# 10_LMS3_RF.net
KiCad netlist of a schematic drawn in Altium Designer
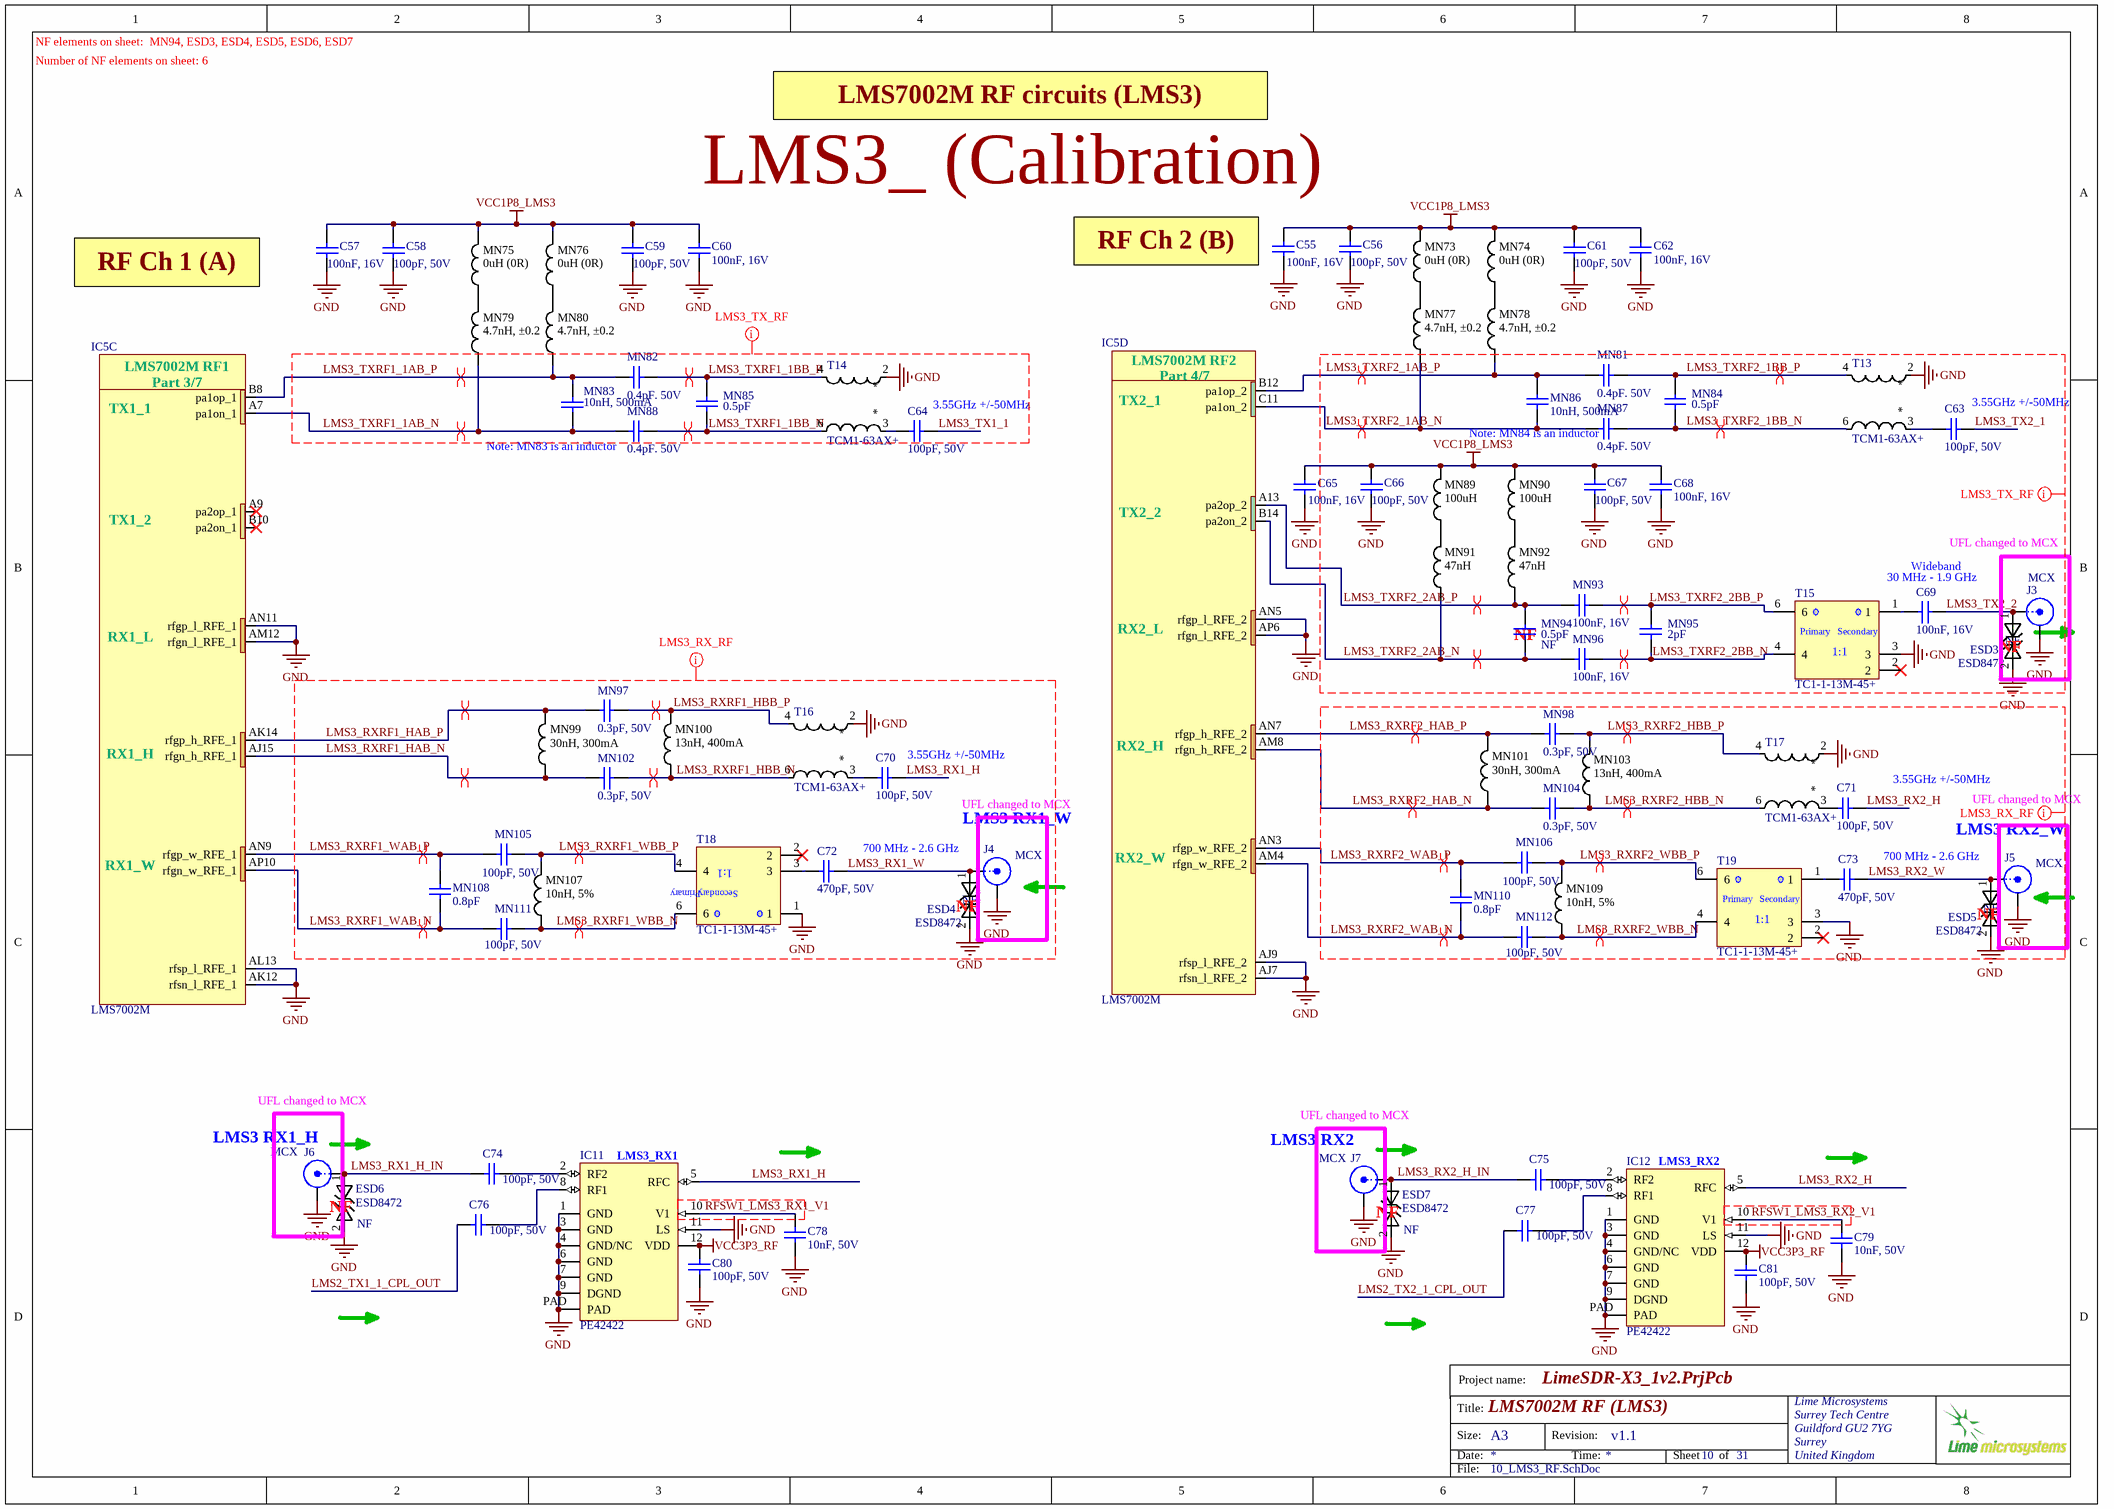
[diagram p0: 10_LMS3_RF.SchDoc]

(export (version "E")
  (design (tool "Eeschema 10.0.6"))
  (components
    (comp (ref "C55")
      (value "100nF, 16V")
      (footprint "CAP0402")
      (fields (field (name "MANUFACTURER") "Murata Electronics") (field (name "TOLERANCE") "10 %"))
      (libsource (lib "") (part "Cap_0402_5"))
    )
    (comp (ref "C56")
      (value "100pF, 50V")
      (footprint "CAP0402")
      (fields (field (name "MANUFACTURER") "Yageo") (field (name "TOLERANCE") "±5%"))
      (libsource (lib "") (part "Cap_0402_2"))
    )
    (comp (ref "C57")
      (value "100nF, 16V")
      (footprint "CAP0402")
      (fields (field (name "MANUFACTURER") "Murata Electronics") (field (name "TOLERANCE") "10 %"))
      (libsource (lib "") (part "Cap_0402_7"))
    )
    (comp (ref "C58")
      (value "100pF, 50V")
      (footprint "CAP0402")
      (fields (field (name "MANUFACTURER") "Yageo") (field (name "TOLERANCE") "±5%"))
      (libsource (lib "") (part "Cap_0402_2"))
    )
    (comp (ref "C59")
      (value "100pF, 50V")
      (footprint "CAP0402")
      (fields (field (name "MANUFACTURER") "Yageo") (field (name "TOLERANCE") "±5%"))
      (libsource (lib "") (part "Cap_0402_2"))
    )
    (comp (ref "C60")
      (value "100nF, 16V")
      (footprint "CAP0402")
      (fields (field (name "MANUFACTURER") "Murata Electronics") (field (name "TOLERANCE") "10 %"))
      (libsource (lib "") (part "Cap_0402_7"))
    )
    (comp (ref "C61")
      (value "100pF, 50V")
      (footprint "CAP0402")
      (fields (field (name "MANUFACTURER") "Yageo") (field (name "TOLERANCE") "±5%"))
      (libsource (lib "") (part "Cap_0402_2"))
    )
    (comp (ref "C62")
      (value "100nF, 16V")
      (footprint "CAP0402")
      (fields (field (name "MANUFACTURER") "Murata Electronics") (field (name "TOLERANCE") "10 %"))
      (libsource (lib "") (part "Cap_0402_5"))
    )
    (comp (ref "C63")
      (value "100pF, 50V")
      (footprint "CAP0402")
      (fields (field (name "TOLERANCE") "±5%") (field (name "MANUFACTURER") "Yageo"))
      (libsource (lib "") (part "Cap_0402_2"))
    )
    (comp (ref "C64")
      (value "100pF, 50V")
      (footprint "CAP0402")
      (fields (field (name "TOLERANCE") "±5%") (field (name "MANUFACTURER") "Yageo"))
      (libsource (lib "") (part "Cap_0402_2"))
    )
    (comp (ref "C65")
      (value "100nF, 16V")
      (footprint "CAP0402")
      (fields (field (name "MANUFACTURER") "Murata Electronics") (field (name "TOLERANCE") "10 %"))
      (libsource (lib "") (part "Cap_0402_1"))
    )
    (comp (ref "C66")
      (value "100pF, 50V")
      (footprint "CAP0402")
      (fields (field (name "MANUFACTURER") "Yageo") (field (name "TOLERANCE") "±5%"))
      (libsource (lib "") (part "Cap_0402_2"))
    )
    (comp (ref "C67")
      (value "100pF, 50V")
      (footprint "CAP0402")
      (fields (field (name "MANUFACTURER") "Yageo") (field (name "TOLERANCE") "±5%"))
      (libsource (lib "") (part "Cap_0402_2"))
    )
    (comp (ref "C68")
      (value "100nF, 16V")
      (footprint "CAP0402")
      (fields (field (name "MANUFACTURER") "Murata Electronics") (field (name "TOLERANCE") "10 %"))
      (libsource (lib "") (part "Cap_0402_1"))
    )
    (comp (ref "C69")
      (value "100nF, 16V")
      (footprint "CAP0402")
      (fields (field (name "MANUFACTURER") "Murata Electronics") (field (name "TOLERANCE") "10 %"))
      (libsource (lib "") (part "Cap_0402_11"))
    )
    (comp (ref "C70")
      (value "100pF, 50V")
      (footprint "CAP0402")
      (fields (field (name "TOLERANCE") "±5%") (field (name "MANUFACTURER") "Yageo"))
      (libsource (lib "") (part "Cap_0402_10"))
    )
    (comp (ref "C71")
      (value "100pF, 50V")
      (footprint "CAP0402")
      (fields (field (name "TOLERANCE") "±5%") (field (name "MANUFACTURER") "Yageo"))
      (libsource (lib "") (part "Cap_0402_10"))
    )
    (comp (ref "C72")
      (value "470pF, 50V")
      (footprint "CAP0402")
      (fields
        (field (name "MANUFACTURER PART NUMBER") "C1005C0G1H471J050BA")
        (field (name "TOLERANCE") "±5%")
        (field (name "MANUFACTURER") "TDK Corporation")
      )
      (libsource (lib "") (part "Cap_0402_3"))
    )
    (comp (ref "C73")
      (value "470pF, 50V")
      (footprint "CAP0402")
      (fields
        (field (name "MANUFACTURER PART NUMBER") "C1005C0G1H471J050BA")
        (field (name "TOLERANCE") "±5%")
        (field (name "MANUFACTURER") "TDK Corporation")
      )
      (libsource (lib "") (part "Cap_0402_3"))
    )
    (comp (ref "C74")
      (value "100pF, 50V")
      (footprint "CAP0402")
      (fields (field (name "TOLERANCE") "±5%") (field (name "MANUFACTURER") "Yageo"))
      (libsource (lib "") (part "Cap_0402_6"))
    )
    (comp (ref "C75")
      (value "100pF, 50V")
      (footprint "CAP0402")
      (fields (field (name "TOLERANCE") "±5%") (field (name "MANUFACTURER") "Yageo"))
      (libsource (lib "") (part "Cap_0402_6"))
    )
    (comp (ref "C76")
      (value "100pF, 50V")
      (footprint "CAP0402")
      (fields (field (name "TOLERANCE") "±5%") (field (name "MANUFACTURER") "Yageo"))
      (libsource (lib "") (part "Cap_0402_6"))
    )
    (comp (ref "C77")
      (value "100pF, 50V")
      (footprint "CAP0402")
      (fields (field (name "TOLERANCE") "±5%") (field (name "MANUFACTURER") "Yageo"))
      (libsource (lib "") (part "Cap_0402_6"))
    )
    (comp (ref "C78")
      (value "10nF, 50V")
      (footprint "CAP0402")
      (fields
        (field (name "MANUFACTURER") "Murata Electronics North America")
        (field (name "TOLERANCE") "±10%")
      )
      (libsource (lib "") (part "Cap_0402_7"))
    )
    (comp (ref "C79")
      (value "10nF, 50V")
      (footprint "CAP0402")
      (fields
        (field (name "MANUFACTURER") "Murata Electronics North America")
        (field (name "TOLERANCE") "±10%")
      )
      (libsource (lib "") (part "Cap_0402_7"))
    )
    (comp (ref "C80")
      (value "100pF, 50V")
      (footprint "CAP0402")
      (fields (field (name "TOLERANCE") "±5%") (field (name "MANUFACTURER") "Yageo"))
      (libsource (lib "") (part "Cap_0402_8"))
    )
    (comp (ref "C81")
      (value "100pF, 50V")
      (footprint "CAP0402")
      (fields (field (name "TOLERANCE") "±5%") (field (name "MANUFACTURER") "Yageo"))
      (libsource (lib "") (part "Cap_0402_8"))
    )
    (comp (ref "ESD3")
      (value "ESD8472")
      (footprint "ESD8472_X3DFN2")
      (fields (field (name "MANUFACTURER") "ON Semiconductor") (field (name "ASSEMBLY INFO") "NF"))
      (libsource (lib "LimeMicroAltiumLib_schLib") (part "ESD8472"))
    )
    (comp (ref "ESD4")
      (value "ESD8472")
      (footprint "ESD8472_X3DFN2")
      (fields (field (name "MANUFACTURER") "ON Semiconductor") (field (name "ASSEMBLY INFO") "NF"))
      (libsource (lib "LimeMicroAltiumLib_schLib") (part "ESD8472"))
    )
    (comp (ref "ESD5")
      (value "ESD8472")
      (footprint "ESD8472_X3DFN2")
      (fields (field (name "MANUFACTURER") "ON Semiconductor") (field (name "ASSEMBLY INFO") "NF"))
      (libsource (lib "LimeMicroAltiumLib_schLib") (part "ESD8472"))
    )
    (comp (ref "ESD6")
      (value "ESD8472")
      (footprint "ESD8472_X3DFN2")
      (fields (field (name "MANUFACTURER") "ON Semiconductor") (field (name "ASSEMBLY INFO") "NF"))
      (libsource (lib "LimeMicroAltiumLib_schLib") (part "ESD8472"))
    )
    (comp (ref "ESD7")
      (value "ESD8472")
      (footprint "ESD8472_X3DFN2")
      (fields (field (name "MANUFACTURER") "ON Semiconductor") (field (name "ASSEMBLY INFO") "NF"))
      (libsource (lib "LimeMicroAltiumLib_schLib") (part "ESD8472"))
    )
    (comp (ref "IC5")
      (value "LMS7002M")
      (footprint "LMS7002M_v5")
      (description "Schematic symbol revision 4. Default footprint - 0.31mm pad")
      (fields (field (name "MANUFACTURER") "Lime Microsystems"))
      (libsource (lib "LimeMicroAltiumLib_schLib_r04") (part "LMS7002Mr4"))
    )
    (comp (ref "IC11")
      (value "PE42422")
      (footprint "PE42422_QFN12")
      (fields (field (name "MANUFACTURER") "Peregrine Semiconductor"))
      (libsource (lib "LimeMicroAltiumLib_schLib") (part "PE42422"))
    )
    (comp (ref "IC12")
      (value "PE42422")
      (footprint "PE42422_QFN12")
      (fields (field (name "MANUFACTURER") "Peregrine Semiconductor"))
      (libsource (lib "LimeMicroAltiumLib_schLib") (part "PE42422"))
    )
    (comp (ref "J3")
      (value "MCX")
      (footprint "MCX_connector_vertical_SM")
      (description "Conn MCX RCP 0Hz to 6GHz 50Ohm Solder ST SMD Gold Over Nickel Stock")
      (fields (field (name "MANUFACTURER") "Bel Cinch"))
      (libsource (lib "LimeMicroAltiumLib_schLib") (part "RF_IF_connector"))
    )
    (comp (ref "J4")
      (value "MCX")
      (footprint "MCX_connector_vertical_SM")
      (description "Conn MCX RCP 0Hz to 6GHz 50Ohm Solder ST SMD Gold Over Nickel Stock")
      (fields (field (name "MANUFACTURER") "Bel Cinch"))
      (libsource (lib "LimeMicroAltiumLib_schLib") (part "RF_IF_connector"))
    )
    (comp (ref "J5")
      (value "MCX")
      (footprint "MCX_connector_vertical_SM")
      (description "Conn MCX RCP 0Hz to 6GHz 50Ohm Solder ST SMD Gold Over Nickel Stock")
      (fields (field (name "MANUFACTURER") "Bel Cinch"))
      (libsource (lib "LimeMicroAltiumLib_schLib") (part "RF_IF_connector"))
    )
    (comp (ref "J6")
      (value "MCX")
      (footprint "MCX_connector_vertical_SM")
      (description "Conn MCX RCP 0Hz to 6GHz 50Ohm Solder ST SMD Gold Over Nickel Stock")
      (fields (field (name "MANUFACTURER") "Bel Cinch"))
      (libsource (lib "LimeMicroAltiumLib_schLib") (part "RF_IF_connector"))
    )
    (comp (ref "J7")
      (value "MCX")
      (footprint "MCX_connector_vertical_SM")
      (description "Conn MCX RCP 0Hz to 6GHz 50Ohm Solder ST SMD Gold Over Nickel Stock")
      (fields (field (name "MANUFACTURER") "Bel Cinch"))
      (libsource (lib "LimeMicroAltiumLib_schLib") (part "RF_IF_connector"))
    )
    (comp (ref "MN73")
      (value "0uH (0R)")
      (footprint "RES0603")
      (fields
        (field (name "MANUFACTURER") "Panasonic Electronic Components")
        (field (name "MANUFACTURER PART NUMBER") "ERJ-3GEY0R00V")
        (field (name "TOLERANCE") "Jumper")
      )
      (libsource (lib "LimeMicroAltiumLib_schLib") (part "Inductor_0603"))
    )
    (comp (ref "MN74")
      (value "0uH (0R)")
      (footprint "RES0603")
      (fields
        (field (name "MANUFACTURER") "Panasonic Electronic Components")
        (field (name "MANUFACTURER PART NUMBER") "ERJ-3GEY0R00V")
        (field (name "TOLERANCE") "Jumper")
      )
      (libsource (lib "LimeMicroAltiumLib_schLib") (part "Inductor_0603"))
    )
    (comp (ref "MN75")
      (value "0uH (0R)")
      (footprint "RES0603")
      (fields
        (field (name "MANUFACTURER") "Panasonic Electronic Components")
        (field (name "MANUFACTURER PART NUMBER") "ERJ-3GEY0R00V")
        (field (name "TOLERANCE") "Jumper")
      )
      (libsource (lib "LimeMicroAltiumLib_schLib") (part "Inductor_0603"))
    )
    (comp (ref "MN76")
      (value "0uH (0R)")
      (footprint "RES0603")
      (fields
        (field (name "MANUFACTURER") "Panasonic Electronic Components")
        (field (name "MANUFACTURER PART NUMBER") "ERJ-3GEY0R00V")
        (field (name "TOLERANCE") "Jumper")
      )
      (libsource (lib "LimeMicroAltiumLib_schLib") (part "Inductor_0603"))
    )
    (comp (ref "MN77")
      (value "4.7nH, ±0.2")
      (footprint "RES0402")
      (fields (field (name "MANUFACTURER") "Murata"))
      (libsource (lib "LimeMicroAltiumLib_schLib") (part "Inductor_0603"))
    )
    (comp (ref "MN78")
      (value "4.7nH, ±0.2")
      (footprint "RES0402")
      (fields (field (name "MANUFACTURER") "Murata"))
      (libsource (lib "LimeMicroAltiumLib_schLib") (part "Inductor_0603"))
    )
    (comp (ref "MN79")
      (value "4.7nH, ±0.2")
      (footprint "RES0402")
      (fields (field (name "MANUFACTURER") "Murata"))
      (libsource (lib "LimeMicroAltiumLib_schLib") (part "Inductor_0603"))
    )
    (comp (ref "MN80")
      (value "4.7nH, ±0.2")
      (footprint "RES0402")
      (fields (field (name "MANUFACTURER") "Murata"))
      (libsource (lib "LimeMicroAltiumLib_schLib") (part "Inductor_0603"))
    )
    (comp (ref "MN81")
      (value "0.4pF. 50V")
      (footprint "CAP0402")
      (fields (field (name "MANUFACTURER") "Murata"))
      (libsource (lib "") (part "Cap_0402_1"))
    )
    (comp (ref "MN82")
      (value "0.4pF. 50V")
      (footprint "CAP0402")
      (fields (field (name "MANUFACTURER") "Murata"))
      (libsource (lib "") (part "Cap_0402_1"))
    )
    (comp (ref "MN83")
      (value "10nH, 500mA")
      (footprint "CAP0402")
      (fields (field (name "MANUFACTURER") "Murata") (field (name "TOLERANCE") "2%"))
      (libsource (lib "") (part "Cap_0402_7"))
    )
    (comp (ref "MN84")
      (value "0.5pF")
      (footprint "CAP0402")
      (fields (field (name "TOLERANCE") "±0.25pF") (field (name "MANUFACTURER") "Yageo"))
      (libsource (lib "") (part "Cap_0402_4"))
    )
    (comp (ref "MN85")
      (value "0.5pF")
      (footprint "CAP0402")
      (fields (field (name "TOLERANCE") "±0.25pF") (field (name "MANUFACTURER") "Yageo"))
      (libsource (lib "") (part "Cap_0402_4"))
    )
    (comp (ref "MN86")
      (value "10nH, 500mA")
      (footprint "CAP0402")
      (fields (field (name "MANUFACTURER") "Murata") (field (name "TOLERANCE") "2%"))
      (libsource (lib "") (part "Cap_0402_7"))
    )
    (comp (ref "MN87")
      (value "0.4pF. 50V")
      (footprint "CAP0402")
      (fields (field (name "MANUFACTURER") "Murata"))
      (libsource (lib "") (part "Cap_0402_9"))
    )
    (comp (ref "MN88")
      (value "0.4pF. 50V")
      (footprint "CAP0402")
      (fields (field (name "MANUFACTURER") "Murata"))
      (libsource (lib "") (part "Cap_0402_9"))
    )
    (comp (ref "MN89")
      (value "100uH")
      (footprint "RES0603")
      (fields
        (field (name "MANUFACTURER") "TDK Corporation")
        (field (name "MANUFACTURER PART NUMBER") "GLFR1608T101M-LR")
        (field (name "TOLERANCE") "±20%")
      )
      (libsource (lib "") (part "Inductor_0603_2"))
    )
    (comp (ref "MN90")
      (value "100uH")
      (footprint "RES0603")
      (fields
        (field (name "MANUFACTURER") "TDK Corporation")
        (field (name "MANUFACTURER PART NUMBER") "GLFR1608T101M-LR")
        (field (name "TOLERANCE") "±20%")
      )
      (libsource (lib "") (part "Inductor_0603_2"))
    )
    (comp (ref "MN91")
      (value "47nH")
      (footprint "RES0402")
      (fields (field (name "MANUFACTURER") "COILCRAFT"))
      (libsource (lib "") (part "Inductor_0603_2"))
    )
    (comp (ref "MN92")
      (value "47nH")
      (footprint "RES0402")
      (fields (field (name "MANUFACTURER") "COILCRAFT"))
      (libsource (lib "") (part "Inductor_0603_2"))
    )
    (comp (ref "MN93")
      (value "100nF, 16V")
      (footprint "CAP0402")
      (fields (field (name "MANUFACTURER") "Murata Electronics") (field (name "TOLERANCE") "10 %"))
      (libsource (lib "") (part "Cap_0402_5"))
    )
    (comp (ref "MN94")
      (value "0.5pF")
      (footprint "CAP0402")
      (fields
        (field (name "ASSEMBLY INFO") "NF")
        (field (name "TOLERANCE") "±0.25pF")
        (field (name "MANUFACTURER") "Yageo")
      )
      (libsource (lib "") (part "Cap_0402_1"))
    )
    (comp (ref "MN95")
      (value "2pF")
      (footprint "CAP0402")
      (fields (field (name "MANUFACTURER PART NUMBER") "04025U2R0BAT2A") (field (name "MANUFACTURER") "AVX"))
      (libsource (lib "") (part "Cap_0402_1"))
    )
    (comp (ref "MN96")
      (value "100nF, 16V")
      (footprint "CAP0402")
      (fields (field (name "MANUFACTURER") "Murata Electronics") (field (name "TOLERANCE") "10 %"))
      (libsource (lib "") (part "Cap_0402_12"))
    )
    (comp (ref "MN97")
      (value "0.3pF, 50V")
      (footprint "CAP0402")
      (fields (field (name "MANUFACTURER") "Johanson"))
      (libsource (lib "LimeMicroAltiumLib_schLib") (part "Cap_0402"))
    )
    (comp (ref "MN98")
      (value "0.3pF, 50V")
      (footprint "CAP0402")
      (fields (field (name "MANUFACTURER") "Johanson"))
      (libsource (lib "LimeMicroAltiumLib_schLib") (part "Cap_0402"))
    )
    (comp (ref "MN99")
      (value "30nH, 300mA")
      (footprint "RES0402")
      (fields (field (name "MANUFACTURER") "TDK") (field (name "TOLERANCE") "5%"))
      (libsource (lib "") (part "Inductor_0603_2"))
    )
    (comp (ref "MN100")
      (value "13nH, 400mA")
      (footprint "RES0402")
      (fields (field (name "MANUFACTURER") "TDK") (field (name "TOLERANCE") "5%"))
      (libsource (lib "") (part "Inductor_0603_3"))
    )
    (comp (ref "MN101")
      (value "30nH, 300mA")
      (footprint "RES0402")
      (fields (field (name "MANUFACTURER") "TDK") (field (name "TOLERANCE") "5%"))
      (libsource (lib "") (part "Inductor_0603_2"))
    )
    (comp (ref "MN102")
      (value "0.3pF, 50V")
      (footprint "CAP0402")
      (fields (field (name "MANUFACTURER") "Johanson"))
      (libsource (lib "LimeMicroAltiumLib_schLib") (part "Cap_0402"))
    )
    (comp (ref "MN103")
      (value "13nH, 400mA")
      (footprint "RES0402")
      (fields (field (name "MANUFACTURER") "TDK") (field (name "TOLERANCE") "5%"))
      (libsource (lib "") (part "Inductor_0603_3"))
    )
    (comp (ref "MN104")
      (value "0.3pF, 50V")
      (footprint "CAP0402")
      (fields (field (name "MANUFACTURER") "Johanson"))
      (libsource (lib "LimeMicroAltiumLib_schLib") (part "Cap_0402"))
    )
    (comp (ref "MN105")
      (value "100pF, 50V")
      (footprint "CAP0402")
      (fields (field (name "TOLERANCE") "±5%") (field (name "MANUFACTURER") "Yageo"))
      (libsource (lib "") (part "Cap_0402_3"))
    )
    (comp (ref "MN106")
      (value "100pF, 50V")
      (footprint "CAP0402")
      (fields (field (name "TOLERANCE") "±5%") (field (name "MANUFACTURER") "Yageo"))
      (libsource (lib "") (part "Cap_0402_3"))
    )
    (comp (ref "MN107")
      (value "10nH, 5%")
      (footprint "RES0402")
      (fields (field (name "MANUFACTURER") "COILCRAFT"))
      (libsource (lib "") (part "Inductor_0603_1"))
    )
    (comp (ref "MN108")
      (value "0.8pF")
      (footprint "CAP0402")
      (fields
        (field (name "TOLERANCE") "±0.1pF")
        (field (name "MANUFACTURER") "Murata Electronics North America")
        (field (name "MANUFACTURER PART NUMBER") "GRM1555C1HR80BA01D")
      )
      (libsource (lib "") (part "Cap_0402_3"))
    )
    (comp (ref "MN109")
      (value "10nH, 5%")
      (footprint "RES0402")
      (fields (field (name "MANUFACTURER") "COILCRAFT"))
      (libsource (lib "") (part "Inductor_0603_1"))
    )
    (comp (ref "MN110")
      (value "0.8pF")
      (footprint "CAP0402")
      (fields
        (field (name "TOLERANCE") "±0.1pF")
        (field (name "MANUFACTURER") "Murata Electronics North America")
        (field (name "MANUFACTURER PART NUMBER") "GRM1555C1HR80BA01D")
      )
      (libsource (lib "") (part "Cap_0402_3"))
    )
    (comp (ref "MN111")
      (value "100pF, 50V")
      (footprint "CAP0402")
      (fields (field (name "TOLERANCE") "±5%") (field (name "MANUFACTURER") "Yageo"))
      (libsource (lib "") (part "Cap_0402_3"))
    )
    (comp (ref "MN112")
      (value "100pF, 50V")
      (footprint "CAP0402")
      (fields (field (name "TOLERANCE") "±5%") (field (name "MANUFACTURER") "Yageo"))
      (libsource (lib "") (part "Cap_0402_3"))
    )
    (comp (ref "T13")
      (value "TCM1-63AX+")
      (footprint "TCM1-63AX+_v2")
      (fields (field (name "MANUFACTURER") "Mini-circuits"))
      (libsource (lib "LimeMicroAltiumLib_schLib") (part "Balun_v2"))
    )
    (comp (ref "T14")
      (value "TCM1-63AX+")
      (footprint "TCM1-63AX+_v2")
      (fields (field (name "MANUFACTURER") "Mini-circuits"))
      (libsource (lib "LimeMicroAltiumLib_schLib") (part "Balun_v2"))
    )
    (comp (ref "T15")
      (value "TC1-1-13M-45+")
      (footprint "TC1-1-13MA+_JA4220-AL_")
      (fields (field (name "MANUFACTURER") "Minicircuits"))
      (libsource (lib "") (part "TC1-1-13M+_1"))
    )
    (comp (ref "T16")
      (value "TCM1-63AX+")
      (footprint "TCM1-63AX+_v2")
      (fields (field (name "MANUFACTURER") "Mini-circuits"))
      (libsource (lib "") (part "Balun_v2_1"))
    )
    (comp (ref "T17")
      (value "TCM1-63AX+")
      (footprint "TCM1-63AX+_v2")
      (fields (field (name "MANUFACTURER") "Mini-circuits"))
      (libsource (lib "") (part "Balun_v2_1"))
    )
    (comp (ref "T18")
      (value "TC1-1-13M-45+")
      (footprint "TC1-1-13MA+_JA4220-AL_")
      (fields (field (name "MANUFACTURER") "Minicircuits"))
      (libsource (lib "LimeMicroAltiumLib_schLib") (part "TC1-1-13M+"))
    )
    (comp (ref "T19")
      (value "TC1-1-13M-45+")
      (footprint "TC1-1-13MA+_JA4220-AL_")
      (fields (field (name "MANUFACTURER") "Minicircuits"))
      (libsource (lib "") (part "TC1-1-13M+_1"))
    )
  )
  (nets
    (net (code "1") (name "/LMS2_TX1_1_CPL_OUT") (class "Default")
      (node (ref "C76") (pin "2") (pinfunction "2_2") (pintype "passive"))
    )
    (net (code "2") (name "/LMS2_TX2_1_CPL_OUT") (class "Default")
      (node (ref "C77") (pin "2") (pinfunction "2_2") (pintype "passive"))
    )
    (net (code "3") (name "/LMS3_RX1_H") (class "Default")
      (node (ref "C70") (pin "1") (pinfunction "1_1") (pintype "passive"))
      (node (ref "IC11") (pin "5") (pinfunction "RFC_5") (pintype "bidirectional"))
    )
    (net (code "4") (name "/LMS3_RX1_H_IN") (class "Default")
      (node (ref "C74") (pin "2") (pinfunction "2_2") (pintype "passive"))
      (node (ref "ESD6") (pin "1") (pinfunction "1_1") (pintype "passive"))
      (node (ref "J6") (pin "1") (pinfunction "X_1") (pintype "passive"))
    )
    (net (code "5") (name "/LMS3_RX1_W") (class "Default")
      (node (ref "C72") (pin "1") (pinfunction "1_1") (pintype "passive"))
      (node (ref "ESD4") (pin "1") (pinfunction "1_1") (pintype "passive"))
      (node (ref "J4") (pin "1") (pinfunction "X_1") (pintype "passive"))
    )
    (net (code "6") (name "/LMS3_RX2_H") (class "Default")
      (node (ref "C71") (pin "1") (pinfunction "1_1") (pintype "passive"))
      (node (ref "IC12") (pin "5") (pinfunction "RFC_5") (pintype "bidirectional"))
    )
    (net (code "7") (name "/LMS3_RX2_H_IN") (class "Default")
      (node (ref "C75") (pin "2") (pinfunction "2_2") (pintype "passive"))
      (node (ref "ESD7") (pin "1") (pinfunction "1_1") (pintype "passive"))
      (node (ref "J7") (pin "1") (pinfunction "X_1") (pintype "passive"))
    )
    (net (code "8") (name "/LMS3_RX2_W") (class "Default")
      (node (ref "C73") (pin "1") (pinfunction "1_1") (pintype "passive"))
      (node (ref "ESD5") (pin "1") (pinfunction "1_1") (pintype "passive"))
      (node (ref "J5") (pin "1") (pinfunction "X_1") (pintype "passive"))
    )
    (net (code "9") (name "/LMS3_RXRF1_HAB_N") (class "Default")
      (node (ref "IC5") (pin "AJ15") (pinfunction "rfgn_h_RFE_1_AJ15") (pintype "passive"))
      (node (ref "MN102") (pin "2") (pinfunction "2_2") (pintype "passive"))
      (node (ref "MN99") (pin "1") (pinfunction "1_1") (pintype "passive"))
    )
    (net (code "10") (name "/LMS3_RXRF1_HAB_P") (class "Default")
      (node (ref "IC5") (pin "AK14") (pinfunction "rfgp_h_RFE_1_AK14") (pintype "passive"))
      (node (ref "MN97") (pin "2") (pinfunction "2_2") (pintype "passive"))
      (node (ref "MN99") (pin "2") (pinfunction "2_2") (pintype "passive"))
    )
    (net (code "11") (name "/LMS3_RXRF1_HBB_N") (class "Default")
      (node (ref "MN100") (pin "1") (pinfunction "1_1") (pintype "passive"))
      (node (ref "MN102") (pin "1") (pinfunction "1_1") (pintype "passive"))
      (node (ref "T16") (pin "6") (pinfunction "6_6") (pintype "passive"))
    )
    (net (code "12") (name "/LMS3_RXRF1_HBB_P") (class "Default")
      (node (ref "MN100") (pin "2") (pinfunction "2_2") (pintype "passive"))
      (node (ref "MN97") (pin "1") (pinfunction "1_1") (pintype "passive"))
      (node (ref "T16") (pin "4") (pinfunction "4_4") (pintype "passive"))
    )
    (net (code "13") (name "/LMS3_RXRF1_WAB_N") (class "Default")
      (node (ref "IC5") (pin "AP10") (pinfunction "rfgn_w_RFE_1_AP10") (pintype "passive"))
      (node (ref "MN108") (pin "2") (pinfunction "2_2") (pintype "passive"))
      (node (ref "MN111") (pin "2") (pinfunction "2_2") (pintype "passive"))
    )
    (net (code "14") (name "/LMS3_RXRF1_WAB_P") (class "Default")
      (node (ref "IC5") (pin "AN9") (pinfunction "rfgp_w_RFE_1_AN9") (pintype "passive"))
      (node (ref "MN105") (pin "2") (pinfunction "2_2") (pintype "passive"))
      (node (ref "MN108") (pin "1") (pinfunction "1_1") (pintype "passive"))
    )
    (net (code "15") (name "/LMS3_RXRF1_WBB_N") (class "Default")
      (node (ref "MN107") (pin "1") (pinfunction "1_1") (pintype "passive"))
      (node (ref "MN111") (pin "1") (pinfunction "1_1") (pintype "passive"))
      (node (ref "T18") (pin "6") (pinfunction "6_6") (pintype "passive"))
    )
    (net (code "16") (name "/LMS3_RXRF1_WBB_P") (class "Default")
      (node (ref "MN105") (pin "1") (pinfunction "1_1") (pintype "passive"))
      (node (ref "MN107") (pin "2") (pinfunction "2_2") (pintype "passive"))
      (node (ref "T18") (pin "4") (pinfunction "4_4") (pintype "passive"))
    )
    (net (code "18") (name "/LMS3_RXRF2_HAB_P") (class "Default")
      (node (ref "IC5") (pin "AN7") (pinfunction "rfgp_h_RFE_2_AN7") (pintype "passive"))
      (node (ref "MN101") (pin "2") (pinfunction "2_2") (pintype "passive"))
      (node (ref "MN98") (pin "2") (pinfunction "2_2") (pintype "passive"))
    )
    (net (code "19") (name "/LMS3_RXRF2_HBB_N") (class "Default")
      (node (ref "MN103") (pin "1") (pinfunction "1_1") (pintype "passive"))
      (node (ref "MN104") (pin "1") (pinfunction "1_1") (pintype "passive"))
      (node (ref "T17") (pin "6") (pinfunction "6_6") (pintype "passive"))
    )
    (net (code "20") (name "/LMS3_RXRF2_HBB_P") (class "Default")
      (node (ref "MN103") (pin "2") (pinfunction "2_2") (pintype "passive"))
      (node (ref "MN98") (pin "1") (pinfunction "1_1") (pintype "passive"))
      (node (ref "T17") (pin "4") (pinfunction "4_4") (pintype "passive"))
    )
    (net (code "21") (name "/LMS3_RXRF2_WAB_N") (class "Default")
      (node (ref "IC5") (pin "AM4") (pinfunction "rfgn_w_RFE_2_AM4") (pintype "passive"))
      (node (ref "MN110") (pin "2") (pinfunction "2_2") (pintype "passive"))
      (node (ref "MN112") (pin "2") (pinfunction "2_2") (pintype "passive"))
    )
    (net (code "22") (name "/LMS3_RXRF2_WAB_P") (class "Default")
      (node (ref "IC5") (pin "AN3") (pinfunction "rfgp_w_RFE_2_AN3") (pintype "passive"))
      (node (ref "MN106") (pin "2") (pinfunction "2_2") (pintype "passive"))
      (node (ref "MN110") (pin "1") (pinfunction "1_1") (pintype "passive"))
    )
    (net (code "23") (name "/LMS3_RXRF2_WBB_N") (class "Default")
      (node (ref "MN109") (pin "1") (pinfunction "1_1") (pintype "passive"))
      (node (ref "MN112") (pin "1") (pinfunction "1_1") (pintype "passive"))
      (node (ref "T19") (pin "4") (pinfunction "4_4") (pintype "passive"))
    )
    (net (code "24") (name "/LMS3_RXRF2_WBB_P") (class "Default")
      (node (ref "MN106") (pin "1") (pinfunction "1_1") (pintype "passive"))
      (node (ref "MN109") (pin "2") (pinfunction "2_2") (pintype "passive"))
      (node (ref "T19") (pin "6") (pinfunction "6_6") (pintype "passive"))
    )
    (net (code "25") (name "/LMS3_TX1_1") (class "Default")
      (node (ref "C64") (pin "1") (pinfunction "1_1") (pintype "passive"))
    )
    (net (code "26") (name "/LMS3_TX2_1") (class "Default")
      (node (ref "C63") (pin "1") (pinfunction "1_1") (pintype "passive"))
    )
    (net (code "27") (name "/LMS3_TX2_2") (class "Default")
      (node (ref "C69") (pin "1") (pinfunction "1_1") (pintype "passive"))
      (node (ref "ESD3") (pin "1") (pinfunction "1_1") (pintype "passive"))
      (node (ref "J3") (pin "1") (pinfunction "X_1") (pintype "passive"))
    )
    (net (code "28") (name "/LMS3_TXRF1_1AB_N") (class "Default")
      (node (ref "IC5") (pin "A7") (pinfunction "pa1on_1_A7") (pintype "passive"))
      (node (ref "MN79") (pin "1") (pinfunction "1_1") (pintype "passive"))
      (node (ref "MN83") (pin "2") (pinfunction "2_2") (pintype "passive"))
      (node (ref "MN88") (pin "2") (pinfunction "2_2") (pintype "passive"))
    )
    (net (code "29") (name "/LMS3_TXRF1_1AB_P") (class "Default")
      (node (ref "IC5") (pin "B8") (pinfunction "pa1op_1_B8") (pintype "passive"))
      (node (ref "MN80") (pin "1") (pinfunction "1_1") (pintype "passive"))
      (node (ref "MN82") (pin "2") (pinfunction "2_2") (pintype "passive"))
      (node (ref "MN83") (pin "1") (pinfunction "1_1") (pintype "passive"))
    )
    (net (code "30") (name "/LMS3_TXRF1_1BB_N") (class "Default")
      (node (ref "MN85") (pin "1") (pinfunction "1_1") (pintype "passive"))
      (node (ref "MN88") (pin "1") (pinfunction "1_1") (pintype "passive"))
      (node (ref "T14") (pin "6") (pinfunction "6_6") (pintype "passive"))
    )
    (net (code "31") (name "/LMS3_TXRF1_1BB_P") (class "Default")
      (node (ref "MN82") (pin "1") (pinfunction "1_1") (pintype "passive"))
      (node (ref "MN85") (pin "2") (pinfunction "2_2") (pintype "passive"))
      (node (ref "T14") (pin "4") (pinfunction "4_4") (pintype "passive"))
    )
    (net (code "32") (name "/LMS3_TXRF2_1AB_N") (class "Default")
      (node (ref "IC5") (pin "C11") (pinfunction "pa1on_2_C11") (pintype "passive"))
      (node (ref "MN77") (pin "1") (pinfunction "1_1") (pintype "passive"))
      (node (ref "MN86") (pin "1") (pinfunction "1_1") (pintype "passive"))
      (node (ref "MN87") (pin "2") (pinfunction "2_2") (pintype "passive"))
    )
    (net (code "33") (name "/LMS3_TXRF2_1AB_P") (class "Default")
      (node (ref "IC5") (pin "B12") (pinfunction "pa1op_2_B12") (pintype "passive"))
      (node (ref "MN78") (pin "1") (pinfunction "1_1") (pintype "passive"))
      (node (ref "MN81") (pin "2") (pinfunction "2_2") (pintype "passive"))
      (node (ref "MN86") (pin "2") (pinfunction "2_2") (pintype "passive"))
    )
    (net (code "34") (name "/LMS3_TXRF2_1BB_N") (class "Default")
      (node (ref "MN84") (pin "1") (pinfunction "1_1") (pintype "passive"))
      (node (ref "MN87") (pin "1") (pinfunction "1_1") (pintype "passive"))
      (node (ref "T13") (pin "6") (pinfunction "6_6") (pintype "passive"))
    )
    (net (code "35") (name "/LMS3_TXRF2_1BB_P") (class "Default")
      (node (ref "MN81") (pin "1") (pinfunction "1_1") (pintype "passive"))
      (node (ref "MN84") (pin "2") (pinfunction "2_2") (pintype "passive"))
      (node (ref "T13") (pin "4") (pinfunction "4_4") (pintype "passive"))
    )
    (net (code "36") (name "/LMS3_TXRF2_2AB_N") (class "Default")
      (node (ref "IC5") (pin "B14") (pinfunction "pa2on_2_B14") (pintype "passive"))
      (node (ref "MN91") (pin "1") (pinfunction "1_1") (pintype "passive"))
      (node (ref "MN94") (pin "1") (pinfunction "1_1") (pintype "passive"))
      (node (ref "MN96") (pin "1") (pinfunction "1_1") (pintype "passive"))
    )
    (net (code "37") (name "/LMS3_TXRF2_2AB_P") (class "Default")
      (node (ref "IC5") (pin "A13") (pinfunction "pa2op_2_A13") (pintype "passive"))
      (node (ref "MN92") (pin "1") (pinfunction "1_1") (pintype "passive"))
      (node (ref "MN93") (pin "2") (pinfunction "2_2") (pintype "passive"))
      (node (ref "MN94") (pin "2") (pinfunction "2_2") (pintype "passive"))
    )
    (net (code "38") (name "/LMS3_TXRF2_2BB_N") (class "Default")
      (node (ref "MN95") (pin "1") (pinfunction "1_1") (pintype "passive"))
      (node (ref "MN96") (pin "2") (pinfunction "2_2") (pintype "passive"))
      (node (ref "T15") (pin "4") (pinfunction "4_4") (pintype "passive"))
    )
    (net (code "39") (name "/LMS3_TXRF2_2BB_P") (class "Default")
      (node (ref "MN93") (pin "1") (pinfunction "1_1") (pintype "passive"))
      (node (ref "MN95") (pin "2") (pinfunction "2_2") (pintype "passive"))
      (node (ref "T15") (pin "6") (pinfunction "6_6") (pintype "passive"))
    )
    (net (code "40") (name "/RFSW1_LMS3_RX1_V1") (class "Default")
      (node (ref "C78") (pin "1") (pinfunction "1_1") (pintype "passive"))
      (node (ref "IC11") (pin "10") (pinfunction "V1_10") (pintype "input"))
    )
    (net (code "41") (name "/RFSW1_LMS3_RX2_V1") (class "Default")
      (node (ref "C79") (pin "1") (pinfunction "1_1") (pintype "passive"))
      (node (ref "IC12") (pin "10") (pinfunction "V1_10") (pintype "input"))
    )
    (net (code "42") (name "GND") (class "Default")
      (node (ref "C55") (pin "1") (pinfunction "1_1") (pintype "passive"))
      (node (ref "C56") (pin "1") (pinfunction "1_1") (pintype "passive"))
      (node (ref "C57") (pin "1") (pinfunction "1_1") (pintype "passive"))
      (node (ref "C58") (pin "1") (pinfunction "1_1") (pintype "passive"))
      (node (ref "C59") (pin "1") (pinfunction "1_1") (pintype "passive"))
      (node (ref "C60") (pin "1") (pinfunction "1_1") (pintype "passive"))
      (node (ref "C61") (pin "1") (pinfunction "1_1") (pintype "passive"))
      (node (ref "C62") (pin "1") (pinfunction "1_1") (pintype "passive"))
      (node (ref "C65") (pin "1") (pinfunction "1_1") (pintype "passive"))
      (node (ref "C66") (pin "1") (pinfunction "1_1") (pintype "passive"))
      (node (ref "C67") (pin "1") (pinfunction "1_1") (pintype "passive"))
      (node (ref "C68") (pin "1") (pinfunction "1_1") (pintype "passive"))
      (node (ref "C78") (pin "2") (pinfunction "2_2") (pintype "passive"))
      (node (ref "C79") (pin "2") (pinfunction "2_2") (pintype "passive"))
      (node (ref "C80") (pin "1") (pinfunction "1_1") (pintype "passive"))
      (node (ref "C81") (pin "1") (pinfunction "1_1") (pintype "passive"))
      (node (ref "ESD3") (pin "2") (pinfunction "2_2") (pintype "passive"))
      (node (ref "ESD4") (pin "2") (pinfunction "2_2") (pintype "passive"))
      (node (ref "ESD5") (pin "2") (pinfunction "2_2") (pintype "passive"))
      (node (ref "ESD6") (pin "2") (pinfunction "2_2") (pintype "passive"))
      (node (ref "ESD7") (pin "2") (pinfunction "2_2") (pintype "passive"))
      (node (ref "IC11") (pin "1") (pinfunction "GND_1") (pintype "passive"))
      (node (ref "IC11") (pin "11") (pinfunction "LS_11") (pintype "input"))
      (node (ref "IC11") (pin "3") (pinfunction "GND_3") (pintype "passive"))
      (node (ref "IC11") (pin "4") (pinfunction "GND/NC_4") (pintype "passive"))
      (node (ref "IC11") (pin "6") (pinfunction "GND_6") (pintype "passive"))
      (node (ref "IC11") (pin "7") (pinfunction "GND_7") (pintype "passive"))
      (node (ref "IC11") (pin "9") (pinfunction "DGND_9") (pintype "passive"))
      (node (ref "IC11") (pin "PAD") (pinfunction "PAD_PAD") (pintype "passive"))
      (node (ref "IC12") (pin "1") (pinfunction "GND_1") (pintype "passive"))
      (node (ref "IC12") (pin "11") (pinfunction "LS_11") (pintype "input"))
      (node (ref "IC12") (pin "3") (pinfunction "GND_3") (pintype "passive"))
      (node (ref "IC12") (pin "4") (pinfunction "GND/NC_4") (pintype "passive"))
      (node (ref "IC12") (pin "6") (pinfunction "GND_6") (pintype "passive"))
      (node (ref "IC12") (pin "7") (pinfunction "GND_7") (pintype "passive"))
      (node (ref "IC12") (pin "9") (pinfunction "DGND_9") (pintype "passive"))
      (node (ref "IC12") (pin "PAD") (pinfunction "PAD_PAD") (pintype "passive"))
      (node (ref "IC5") (pin "AJ7") (pinfunction "rfsn_l_RFE_2_AJ7") (pintype "passive"))
      (node (ref "IC5") (pin "AJ9") (pinfunction "rfsp_l_RFE_2_AJ9") (pintype "passive"))
      (node (ref "IC5") (pin "AK12") (pinfunction "rfsn_l_RFE_1_AK12") (pintype "passive"))
      (node (ref "IC5") (pin "AL13") (pinfunction "rfsp_l_RFE_1_AL13") (pintype "passive"))
      (node (ref "IC5") (pin "AM12") (pinfunction "rfgn_l_RFE_1_AM12") (pintype "passive"))
      (node (ref "IC5") (pin "AN11") (pinfunction "rfgp_l_RFE_1_AN11") (pintype "passive"))
      (node (ref "IC5") (pin "AN5") (pinfunction "rfgp_l_RFE_2_AN5") (pintype "passive"))
      (node (ref "IC5") (pin "AP6") (pinfunction "rfgn_l_RFE_2_AP6") (pintype "passive"))
      (node (ref "J3") (pin "2") (pinfunction "Y_2") (pintype "passive"))
      (node (ref "J4") (pin "2") (pinfunction "Y_2") (pintype "passive"))
      (node (ref "J5") (pin "2") (pinfunction "Y_2") (pintype "passive"))
      (node (ref "J6") (pin "2") (pinfunction "Y_2") (pintype "passive"))
      (node (ref "J7") (pin "2") (pinfunction "Y_2") (pintype "passive"))
      (node (ref "T13") (pin "2") (pinfunction "2_2") (pintype "passive"))
      (node (ref "T14") (pin "2") (pinfunction "2_2") (pintype "passive"))
      (node (ref "T15") (pin "3") (pinfunction "3_3") (pintype "passive"))
      (node (ref "T16") (pin "2") (pinfunction "2_2") (pintype "passive"))
      (node (ref "T17") (pin "2") (pinfunction "2_2") (pintype "passive"))
      (node (ref "T18") (pin "1") (pinfunction "1_1") (pintype "passive"))
      (node (ref "T19") (pin "3") (pinfunction "3_3") (pintype "passive"))
    )
    (net (code "43") (name "Net-(C63-Pad2)") (class "Default")
      (node (ref "C63") (pin "2") (pinfunction "2_2") (pintype "passive"))
      (node (ref "T13") (pin "3") (pinfunction "3_3") (pintype "passive"))
    )
    (net (code "44") (name "Net-(C64-Pad2)") (class "Default")
      (node (ref "C64") (pin "2") (pinfunction "2_2") (pintype "passive"))
      (node (ref "T14") (pin "3") (pinfunction "3_3") (pintype "passive"))
    )
    (net (code "45") (name "Net-(C69-Pad2)") (class "Default")
      (node (ref "C69") (pin "2") (pinfunction "2_2") (pintype "passive"))
      (node (ref "T15") (pin "1") (pinfunction "1_1") (pintype "passive"))
    )
    (net (code "46") (name "Net-(C70-Pad2)") (class "Default")
      (node (ref "C70") (pin "2") (pinfunction "2_2") (pintype "passive"))
      (node (ref "T16") (pin "3") (pinfunction "3_3") (pintype "passive"))
    )
    (net (code "47") (name "Net-(C71-Pad2)") (class "Default")
      (node (ref "C71") (pin "2") (pinfunction "2_2") (pintype "passive"))
      (node (ref "T17") (pin "3") (pinfunction "3_3") (pintype "passive"))
    )
    (net (code "48") (name "Net-(C72-Pad2)") (class "Default")
      (node (ref "C72") (pin "2") (pinfunction "2_2") (pintype "passive"))
      (node (ref "T18") (pin "3") (pinfunction "3_3") (pintype "passive"))
    )
    (net (code "49") (name "Net-(C73-Pad2)") (class "Default")
      (node (ref "C73") (pin "2") (pinfunction "2_2") (pintype "passive"))
      (node (ref "T19") (pin "1") (pinfunction "1_1") (pintype "passive"))
    )
    (net (code "50") (name "Net-(IC5D-rfgn_h_RFE_2)") (class "Default")
      (node (ref "IC5") (pin "AM8") (pinfunction "rfgn_h_RFE_2_AM8") (pintype "passive"))
      (node (ref "MN101") (pin "1") (pinfunction "1_1") (pintype "passive"))
      (node (ref "MN104") (pin "2") (pinfunction "2_2") (pintype "passive"))
    )
    (net (code "51") (name "Net-(IC11-RF1)") (class "Default")
      (node (ref "C76") (pin "1") (pinfunction "1_1") (pintype "passive"))
      (node (ref "IC11") (pin "8") (pinfunction "RF1_8") (pintype "bidirectional"))
    )
    (net (code "52") (name "Net-(IC11-RF2)") (class "Default")
      (node (ref "C74") (pin "1") (pinfunction "1_1") (pintype "passive"))
      (node (ref "IC11") (pin "2") (pinfunction "RF2_2") (pintype "bidirectional"))
    )
    (net (code "53") (name "Net-(IC12-RF1)") (class "Default")
      (node (ref "C77") (pin "1") (pinfunction "1_1") (pintype "passive"))
      (node (ref "IC12") (pin "8") (pinfunction "RF1_8") (pintype "bidirectional"))
    )
    (net (code "54") (name "Net-(IC12-RF2)") (class "Default")
      (node (ref "C75") (pin "1") (pinfunction "1_1") (pintype "passive"))
      (node (ref "IC12") (pin "2") (pinfunction "RF2_2") (pintype "bidirectional"))
    )
    (net (code "55") (name "Net-(MN73-Pad1)") (class "Default")
      (node (ref "MN73") (pin "1") (pinfunction "1_1") (pintype "passive"))
      (node (ref "MN77") (pin "2") (pinfunction "2_2") (pintype "passive"))
    )
    (net (code "56") (name "Net-(MN74-Pad1)") (class "Default")
      (node (ref "MN74") (pin "1") (pinfunction "1_1") (pintype "passive"))
      (node (ref "MN78") (pin "2") (pinfunction "2_2") (pintype "passive"))
    )
    (net (code "57") (name "Net-(MN75-Pad1)") (class "Default")
      (node (ref "MN75") (pin "1") (pinfunction "1_1") (pintype "passive"))
      (node (ref "MN79") (pin "2") (pinfunction "2_2") (pintype "passive"))
    )
    (net (code "58") (name "Net-(MN76-Pad1)") (class "Default")
      (node (ref "MN76") (pin "1") (pinfunction "1_1") (pintype "passive"))
      (node (ref "MN80") (pin "2") (pinfunction "2_2") (pintype "passive"))
    )
    (net (code "59") (name "Net-(MN89-Pad1)") (class "Default")
      (node (ref "MN89") (pin "1") (pinfunction "1_1") (pintype "passive"))
      (node (ref "MN91") (pin "2") (pinfunction "2_2") (pintype "passive"))
    )
    (net (code "60") (name "Net-(MN90-Pad1)") (class "Default")
      (node (ref "MN90") (pin "1") (pinfunction "1_1") (pintype "passive"))
      (node (ref "MN92") (pin "2") (pinfunction "2_2") (pintype "passive"))
    )
    (net (code "61") (name "VCC1P8_LMS3") (class "Default")
      (node (ref "C55") (pin "2") (pinfunction "2_2") (pintype "passive"))
      (node (ref "C56") (pin "2") (pinfunction "2_2") (pintype "passive"))
      (node (ref "C57") (pin "2") (pinfunction "2_2") (pintype "passive"))
      (node (ref "C58") (pin "2") (pinfunction "2_2") (pintype "passive"))
      (node (ref "C59") (pin "2") (pinfunction "2_2") (pintype "passive"))
      (node (ref "C60") (pin "2") (pinfunction "2_2") (pintype "passive"))
      (node (ref "C61") (pin "2") (pinfunction "2_2") (pintype "passive"))
      (node (ref "C62") (pin "2") (pinfunction "2_2") (pintype "passive"))
      (node (ref "C65") (pin "2") (pinfunction "2_2") (pintype "passive"))
      (node (ref "C66") (pin "2") (pinfunction "2_2") (pintype "passive"))
      (node (ref "C67") (pin "2") (pinfunction "2_2") (pintype "passive"))
      (node (ref "C68") (pin "2") (pinfunction "2_2") (pintype "passive"))
      (node (ref "MN73") (pin "2") (pinfunction "2_2") (pintype "passive"))
      (node (ref "MN74") (pin "2") (pinfunction "2_2") (pintype "passive"))
      (node (ref "MN75") (pin "2") (pinfunction "2_2") (pintype "passive"))
      (node (ref "MN76") (pin "2") (pinfunction "2_2") (pintype "passive"))
      (node (ref "MN89") (pin "2") (pinfunction "2_2") (pintype "passive"))
      (node (ref "MN90") (pin "2") (pinfunction "2_2") (pintype "passive"))
    )
    (net (code "62") (name "VCC3P3_RF") (class "Default")
      (node (ref "C80") (pin "2") (pinfunction "2_2") (pintype "passive"))
      (node (ref "C81") (pin "2") (pinfunction "2_2") (pintype "passive"))
      (node (ref "IC11") (pin "12") (pinfunction "VDD_12") (pintype "power_in"))
      (node (ref "IC12") (pin "12") (pinfunction "VDD_12") (pintype "power_in"))
    )
    (net (code "63") (name "unconnected-(IC5C-pa2on_1-PadB10)") (class "Default")
      (node (ref "IC5") (pin "B10") (pinfunction "pa2on_1_B10") (pintype "passive+no_connect"))
    )
    (net (code "64") (name "unconnected-(IC5C-pa2op_1-PadA9)") (class "Default")
      (node (ref "IC5") (pin "A9") (pinfunction "pa2op_1_A9") (pintype "passive+no_connect"))
    )
    (net (code "65") (name "unconnected-(T15-Pad2)") (class "Default")
      (node (ref "T15") (pin "2") (pinfunction "2_2") (pintype "passive+no_connect"))
    )
    (net (code "66") (name "unconnected-(T18-Pad2)") (class "Default")
      (node (ref "T18") (pin "2") (pinfunction "2_2") (pintype "passive+no_connect"))
    )
    (net (code "67") (name "unconnected-(T19-Pad2)") (class "Default")
      (node (ref "T19") (pin "2") (pinfunction "2_2") (pintype "passive+no_connect"))
    )
  )
)
